# Connectors.net
KiCad netlist of a schematic drawn in Altium Designer
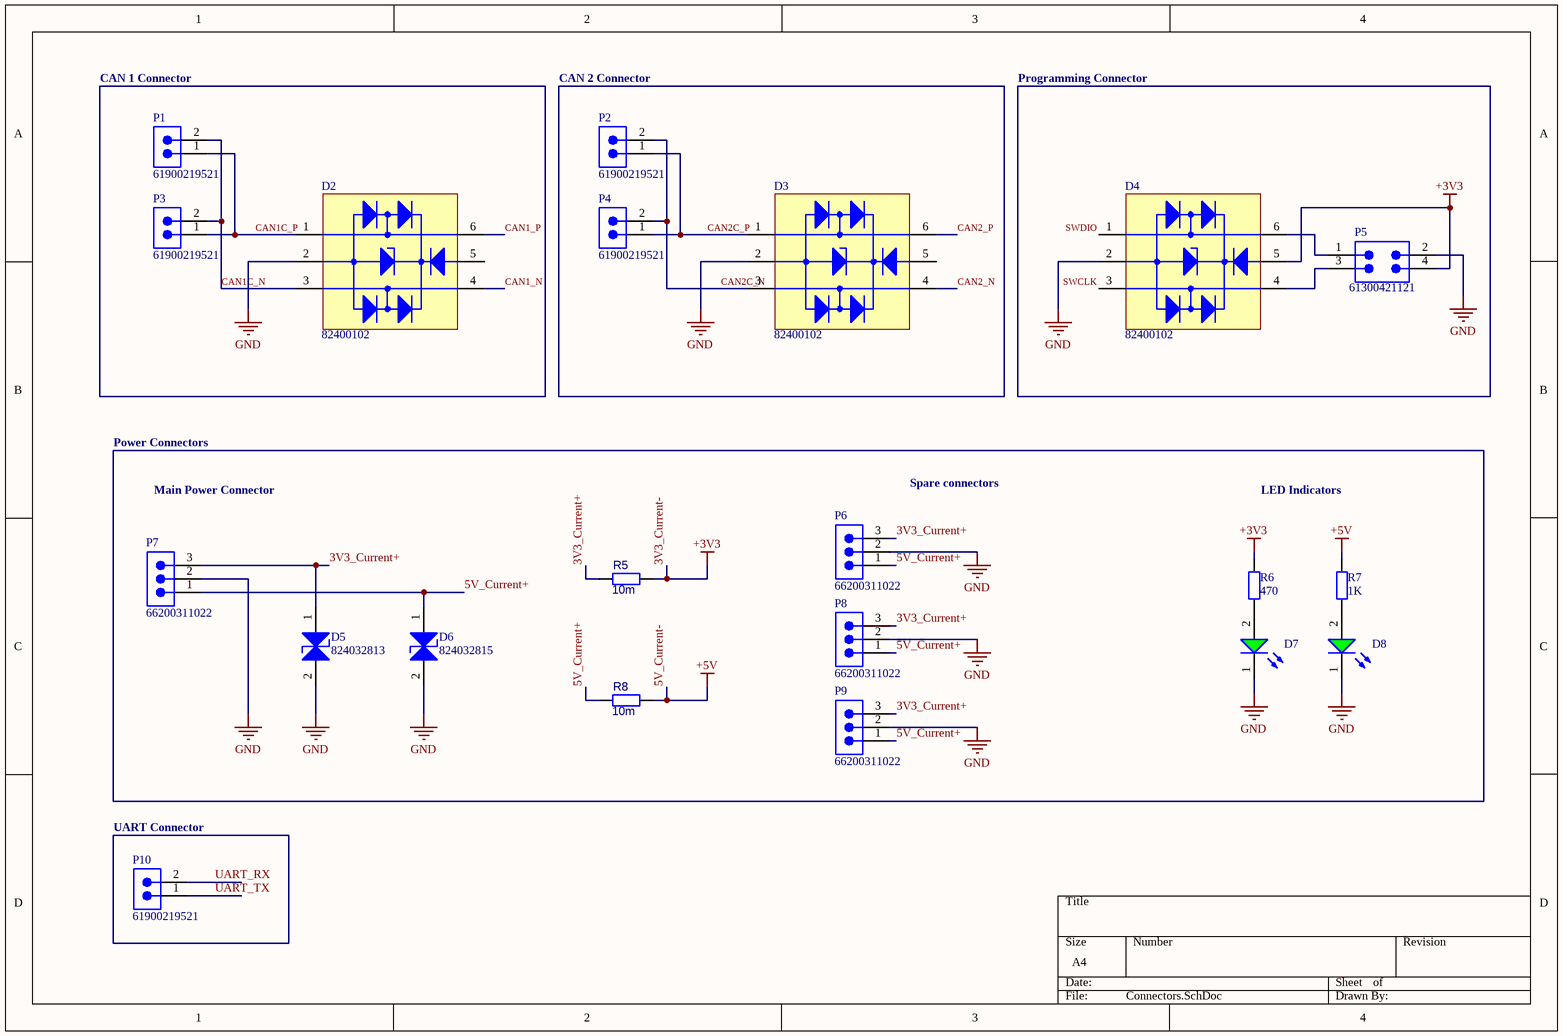
[diagram p0: Connectors.SchDoc]

(export (version "E")
  (design (tool "Eeschema 10.0.6"))
  (components
    (comp (ref "D2")
      (value "82400102")
      (footprint "WE-TVS_SOT23-6L")
      (description "WE-TVS TVS Diode – High Speed Series, SOT23-6L, 2+1 Channel, 5V, 2pF")
      (fields (field (name "MANUFACTURER") "Wurth Elektronik"))
      (libsource (lib "LEEM UPM") (part "82400152"))
    )
    (comp (ref "D3")
      (value "82400102")
      (footprint "WE-TVS_SOT23-6L")
      (description "WE-TVS TVS Diode – High Speed Series, SOT23-6L, 2+1 Channel, 5V, 2pF")
      (fields (field (name "MANUFACTURER") "Wurth Elektronik"))
      (libsource (lib "LEEM UPM") (part "82400152"))
    )
    (comp (ref "D4")
      (value "82400102")
      (footprint "WE-TVS_SOT23-6L")
      (description "WE-TVS TVS Diode – High Speed Series, SOT23-6L, 2+1 Channel, 5V, 2pF")
      (fields (field (name "MANUFACTURER") "Wurth Elektronik"))
      (libsource (lib "LEEM UPM") (part "82400152"))
    )
    (comp (ref "D5")
      (value "824032813")
      (footprint "WE-TVS_DFN1610-2L")
      (description "824032813 Tvs Diode, Bidir, 3.3V, Dfn1610 Rohs Compliant: Yes")
      (libsource (lib "Altium Content Vault") (part "Diode_1 Channel_Bidirectional"))
    )
    (comp (ref "D6")
      (value "824032815")
      (footprint "WE-TVS_DFN1610-2L")
      (description "824032815 Tvs Diode, Bidir, 5V, Dfn1610 Rohs Compliant: Yes")
      (libsource (lib "Altium Content Vault") (part "Diode_1 Channel_Bidirectional"))
    )
    (comp (ref "D7")
      (value "150080GS75000")
      (footprint "WL-SMCW_0805_150080xx75000")
      (description "WL-SMCW Mono-color Chip LED Waterclear, SMT, size 0805, Green, 3.2V, 140°")
      (fields (field (name "MANUFACTURER") "Wurth Elektronik"))
      (libsource (lib "LEEM UPM") (part "150120VS87000"))
    )
    (comp (ref "D8")
      (value "150080GS75000")
      (footprint "WL-SMCW_0805_150080xx75000")
      (description "WL-SMCW Mono-color Chip LED Waterclear, SMT, size 0805, Green, 3.2V, 140°")
      (fields (field (name "MANUFACTURER") "Wurth Elektronik"))
      (libsource (lib "LEEM UPM") (part "150120VS87000"))
    )
    (comp (ref "P1")
      (value "61900219521")
      (footprint "61900219521")
      (description "WR-WTB THT Male Right Angled Top Locking Header, pitch 2.54mm, 2pins")
      (fields (field (name "MANUFACTURER") "Wurth Elektronik"))
      (libsource (lib "LEEM UPM") (part "679302124022"))
    )
    (comp (ref "P2")
      (value "61900219521")
      (footprint "61900219521")
      (description "WR-WTB THT Male Right Angled Top Locking Header, pitch 2.54mm, 2pins")
      (fields (field (name "MANUFACTURER") "Wurth Elektronik"))
      (libsource (lib "LEEM UPM") (part "679302124022"))
    )
    (comp (ref "P3")
      (value "61900219521")
      (footprint "61900219521")
      (description "WR-WTB THT Male Right Angled Top Locking Header, pitch 2.54mm, 2pins")
      (fields (field (name "MANUFACTURER") "Wurth Elektronik"))
      (libsource (lib "LEEM UPM") (part "679302124022"))
    )
    (comp (ref "P4")
      (value "61900219521")
      (footprint "61900219521")
      (description "WR-WTB THT Male Right Angled Top Locking Header, pitch 2.54mm, 2pins")
      (fields (field (name "MANUFACTURER") "Wurth Elektronik"))
      (libsource (lib "LEEM UPM") (part "679302124022"))
    )
    (comp (ref "P5")
      (value "61300421121")
      (footprint "61300421121")
      (libsource (lib "LEEM UPM") (part "Header_Male_2R_04P"))
    )
    (comp (ref "P6")
      (value "66200311022")
      (footprint "66200311022")
      (libsource (lib "Altium Content Vault") (part "Header_Male_1R_03P"))
    )
    (comp (ref "P7")
      (value "66200311022")
      (footprint "66200311022")
      (libsource (lib "Altium Content Vault") (part "Header_Male_1R_03P"))
    )
    (comp (ref "P8")
      (value "66200311022")
      (footprint "66200311022")
      (libsource (lib "Altium Content Vault") (part "Header_Male_1R_03P"))
    )
    (comp (ref "P9")
      (value "66200311022")
      (footprint "66200311022")
      (libsource (lib "Altium Content Vault") (part "Header_Male_1R_03P"))
    )
    (comp (ref "P10")
      (value "61900219521")
      (footprint "61900219521")
      (description "WR-WTB THT Male Right Angled Top Locking Header, pitch 2.54mm, 2pins")
      (fields (field (name "MANUFACTURER") "Wurth Elektronik"))
      (libsource (lib "LEEM UPM") (part "679302124022"))
    )
    (comp (ref "R5")
      (value "10m")
      (footprint "580070763010-Footprint-1")
      (description "Res, 0R01, 1%, 2W, Metal Foil, 0612 Rohs Compliant: Yes")
      (libsource (lib "LEEM UPM") (part "RES-2"))
    )
    (comp (ref "R6")
      (value "470")
      (footprint "WRIS-RSKS_0603_Reflow")
      (description "WRIS-RSKS Thick Film Resistor, size 0603, 470Ohm, 100mW")
      (fields
        (field (name "MANUFACTURER") "Wurth Elektronik")
        (field (name "MANUFACTURER PART NUMBER") "560112116067")
      )
      (libsource (lib "LEEM UPM") (part "560112140010"))
    )
    (comp (ref "R7")
      (value "1K")
      (footprint "WRIS-RSKS_0603_Reflow")
      (description "WRIS-RSKS Thick Film Resistor, size 0603, 1000Ohm, 100mW")
      (fields
        (field (name "MANUFACTURER PART NUMBER") "560112116014")
        (field (name "MANUFACTURER") "Wurth Elektronik")
      )
      (libsource (lib "LEEM UPM") (part "560112140010"))
    )
    (comp (ref "R8")
      (value "10m")
      (footprint "580070763010-Footprint-1")
      (description "Res, 0R01, 1%, 2W, Metal Foil, 0612 Rohs Compliant: Yes")
      (libsource (lib "LEEM UPM") (part "RES-2"))
    )
  )
  (nets
    (net (code "1") (name "+3V3") (class "Default")
      (node (ref "D4") (pin "5") (pinfunction "VDD_5") (pintype "passive"))
      (node (ref "P5") (pin "4") (pinfunction "4_4") (pintype "passive"))
      (node (ref "R5") (pin "2") (pinfunction "2_2") (pintype "passive"))
      (node (ref "R6") (pin "2") (pinfunction "2_2") (pintype "passive"))
    )
    (net (code "2") (name "+5V") (class "Default")
      (node (ref "R7") (pin "2") (pinfunction "2_2") (pintype "passive"))
      (node (ref "R8") (pin "2") (pinfunction "2_2") (pintype "passive"))
    )
    (net (code "3") (name "/3V3_Current+") (class "Default")
      (node (ref "D5") (pin "1") (pinfunction "I/O_1_1") (pintype "passive"))
      (node (ref "P6") (pin "3") (pinfunction "3_3") (pintype "passive"))
      (node (ref "P7") (pin "3") (pinfunction "3_3") (pintype "passive"))
      (node (ref "P8") (pin "3") (pinfunction "3_3") (pintype "passive"))
      (node (ref "P9") (pin "3") (pinfunction "3_3") (pintype "passive"))
      (node (ref "R5") (pin "1") (pinfunction "1_1") (pintype "passive"))
    )
    (net (code "4") (name "/5V_Current+") (class "Default")
      (node (ref "D6") (pin "1") (pinfunction "I/O_1_1") (pintype "passive"))
      (node (ref "P6") (pin "1") (pinfunction "1_1") (pintype "passive"))
      (node (ref "P7") (pin "1") (pinfunction "1_1") (pintype "passive"))
      (node (ref "P8") (pin "1") (pinfunction "1_1") (pintype "passive"))
      (node (ref "P9") (pin "1") (pinfunction "1_1") (pintype "passive"))
      (node (ref "R8") (pin "1") (pinfunction "1_1") (pintype "passive"))
    )
    (net (code "5") (name "/CAN1C_N") (class "Default")
      (node (ref "D2") (pin "3") (pinfunction "I/O_2_3") (pintype "passive"))
      (node (ref "P1") (pin "2") (pinfunction "2_2") (pintype "passive"))
      (node (ref "P3") (pin "2") (pinfunction "2_2") (pintype "passive"))
    )
    (net (code "6") (name "/CAN1C_P") (class "Default")
      (node (ref "D2") (pin "1") (pinfunction "I/O_1_1") (pintype "passive"))
      (node (ref "P1") (pin "1") (pinfunction "1_1") (pintype "passive"))
      (node (ref "P3") (pin "1") (pinfunction "1_1") (pintype "passive"))
    )
    (net (code "7") (name "/CAN1_N") (class "Default")
      (node (ref "D2") (pin "4") (pinfunction "I/O_2_4") (pintype "passive"))
    )
    (net (code "8") (name "/CAN1_P") (class "Default")
      (node (ref "D2") (pin "6") (pinfunction "I/O_1_6") (pintype "passive"))
    )
    (net (code "9") (name "/CAN2C_N") (class "Default")
      (node (ref "D3") (pin "3") (pinfunction "I/O_2_3") (pintype "passive"))
      (node (ref "P2") (pin "2") (pinfunction "2_2") (pintype "passive"))
      (node (ref "P4") (pin "2") (pinfunction "2_2") (pintype "passive"))
    )
    (net (code "10") (name "/CAN2C_P") (class "Default")
      (node (ref "D3") (pin "1") (pinfunction "I/O_1_1") (pintype "passive"))
      (node (ref "P2") (pin "1") (pinfunction "1_1") (pintype "passive"))
      (node (ref "P4") (pin "1") (pinfunction "1_1") (pintype "passive"))
    )
    (net (code "11") (name "/CAN2_N") (class "Default")
      (node (ref "D3") (pin "4") (pinfunction "I/O_2_4") (pintype "passive"))
    )
    (net (code "12") (name "/CAN2_P") (class "Default")
      (node (ref "D3") (pin "6") (pinfunction "I/O_1_6") (pintype "passive"))
    )
    (net (code "13") (name "/SWCLK") (class "Default")
      (node (ref "D4") (pin "3") (pinfunction "I/O_2_3") (pintype "passive"))
    )
    (net (code "14") (name "/SWDIO") (class "Default")
      (node (ref "D4") (pin "1") (pinfunction "I/O_1_1") (pintype "passive"))
    )
    (net (code "15") (name "/UART_RX") (class "Default")
      (node (ref "P10") (pin "2") (pinfunction "2_2") (pintype "passive"))
    )
    (net (code "16") (name "/UART_TX") (class "Default")
      (node (ref "P10") (pin "1") (pinfunction "1_1") (pintype "passive"))
    )
    (net (code "17") (name "GND") (class "Default")
      (node (ref "D2") (pin "2") (pinfunction "GND_2") (pintype "passive"))
      (node (ref "D3") (pin "2") (pinfunction "GND_2") (pintype "passive"))
      (node (ref "D4") (pin "2") (pinfunction "GND_2") (pintype "passive"))
      (node (ref "D5") (pin "2") (pinfunction "GND_2") (pintype "passive"))
      (node (ref "D6") (pin "2") (pinfunction "GND_2") (pintype "passive"))
      (node (ref "D7") (pin "1") (pinfunction "K_1") (pintype "passive"))
      (node (ref "D8") (pin "1") (pinfunction "K_1") (pintype "passive"))
      (node (ref "P5") (pin "2") (pinfunction "2_2") (pintype "passive"))
      (node (ref "P6") (pin "2") (pinfunction "2_2") (pintype "passive"))
      (node (ref "P7") (pin "2") (pinfunction "2_2") (pintype "passive"))
      (node (ref "P8") (pin "2") (pinfunction "2_2") (pintype "passive"))
      (node (ref "P9") (pin "2") (pinfunction "2_2") (pintype "passive"))
    )
    (net (code "18") (name "Net-(D4-I{slash}O_1-Pad6)") (class "Default")
      (node (ref "D4") (pin "6") (pinfunction "I/O_1_6") (pintype "passive"))
      (node (ref "P5") (pin "1") (pinfunction "1_1") (pintype "passive"))
    )
    (net (code "19") (name "Net-(D4-I{slash}O_2-Pad4)") (class "Default")
      (node (ref "D4") (pin "4") (pinfunction "I/O_2_4") (pintype "passive"))
      (node (ref "P5") (pin "3") (pinfunction "3_3") (pintype "passive"))
    )
    (net (code "20") (name "Net-(D7-A)") (class "Default")
      (node (ref "D7") (pin "2") (pinfunction "A_2") (pintype "passive"))
      (node (ref "R6") (pin "1") (pinfunction "1_1") (pintype "passive"))
    )
    (net (code "21") (name "Net-(D8-A)") (class "Default")
      (node (ref "D8") (pin "2") (pinfunction "A_2") (pintype "passive"))
      (node (ref "R7") (pin "1") (pinfunction "1_1") (pintype "passive"))
    )
    (net (code "22") (name "unconnected-(D2-VDD-Pad5)") (class "Default")
      (node (ref "D2") (pin "5") (pinfunction "VDD_5") (pintype "passive"))
    )
    (net (code "23") (name "unconnected-(D3-VDD-Pad5)") (class "Default")
      (node (ref "D3") (pin "5") (pinfunction "VDD_5") (pintype "passive"))
    )
  )
)
